# LoRa_Com.net
KiCad netlist of a schematic drawn in Altium Designer
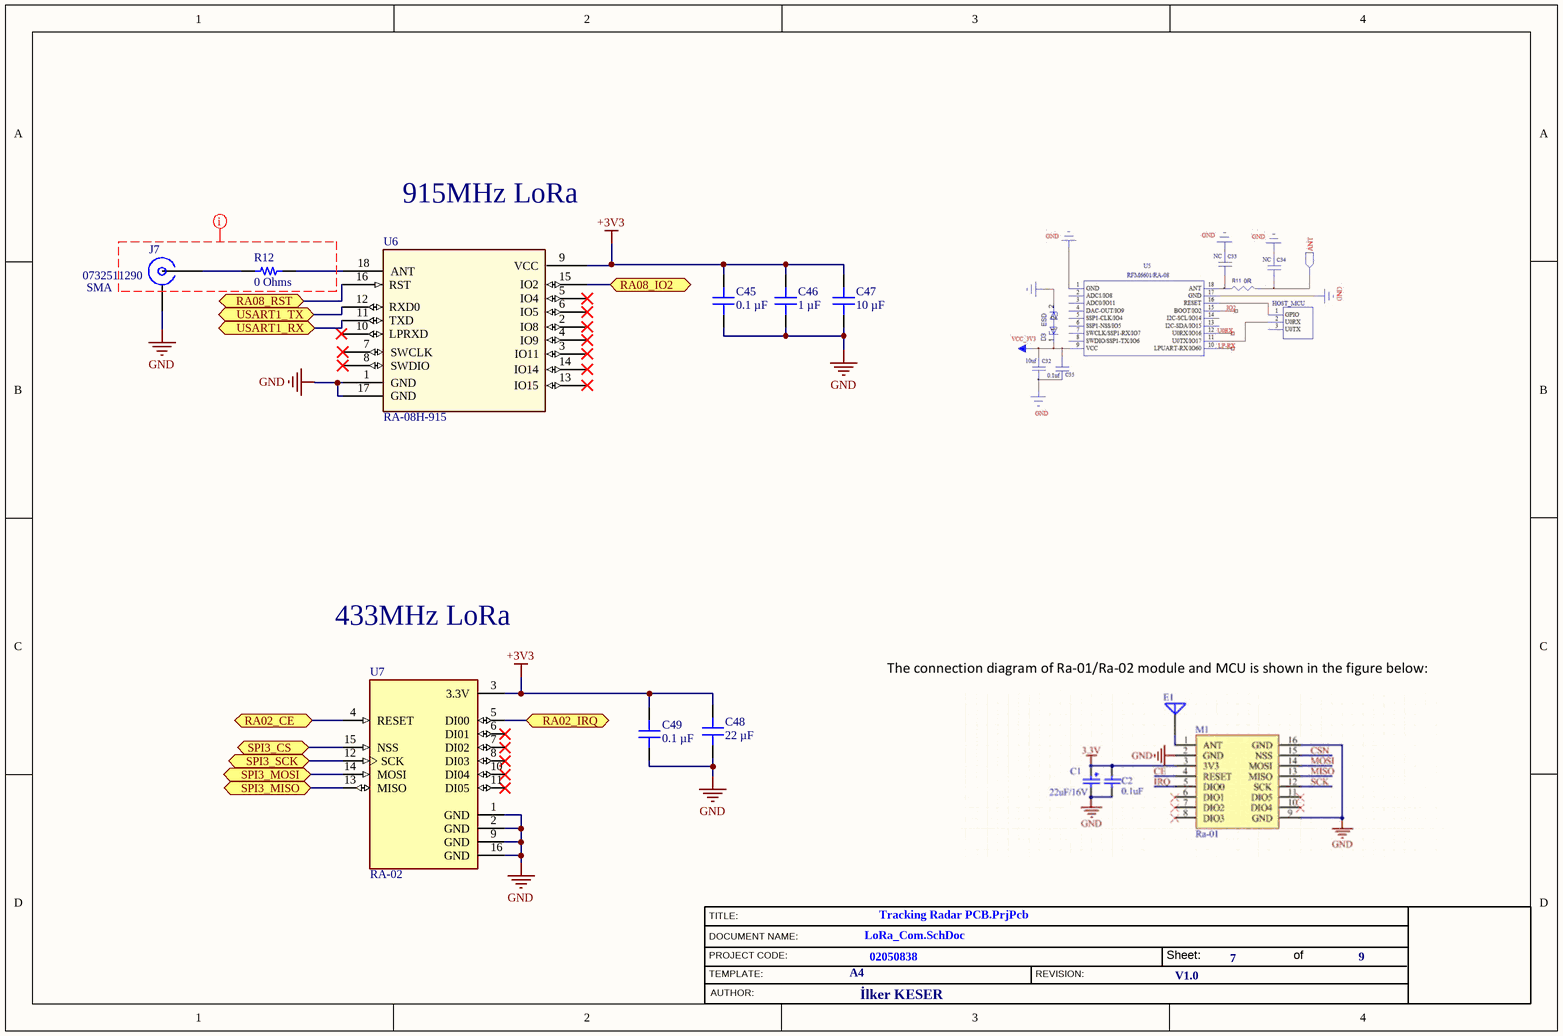
[diagram p0: LoRa_Com.SchDoc]

(export (version "E")
  (design (tool "Eeschema 10.0.6"))
  (components
    (comp (ref "C45")
      (value "0.1 µF")
      (footprint "CAP 0402_1005")
      (description "CAP CER 0.1UF 6.3V X5R 0402")
      (fields
        (field (name "PART NUMBER") "C0402C104M9PAC7867")
        (field (name "CAPACITANCE") "0.1 µF")
        (field (name "MANUFACTURER") "KEMET")
      )
      (libsource (lib "Celestial Altium Library - altium_library") (part "Capacitor"))
    )
    (comp (ref "C46")
      (value "1 µF")
      (footprint "CAP 0402_1005")
      (description "CAP CER 1UF 6.3V X5R 0402")
      (fields
        (field (name "PART NUMBER") "GRM152R60J105ME15D")
        (field (name "CAPACITANCE") "1 µF")
        (field (name "MANUFACTURER") "Murata Electronics")
      )
      (libsource (lib "Celestial Altium Library - altium_library") (part "Capacitor"))
    )
    (comp (ref "C47")
      (value "10 µF")
      (footprint "MURATA GRM188 0603_1608")
      (description "CAP CER 10UF 10V X5R 0603")
      (fields
        (field (name "PART NUMBER") "GRM188R61A106MAALD")
        (field (name "CAPACITANCE") "10 µF")
        (field (name "MANUFACTURER") "Murata Electronics")
      )
      (libsource (lib "Celestial Altium Library - altium_library") (part "Capacitor"))
    )
    (comp (ref "C48")
      (value "22 µF")
      (footprint "MURATA GRM188 0603_1608")
      (description "CAP CER 22UF 16V X5S 0603")
      (fields
        (field (name "PART NUMBER") "GRM188C61C226ME01W")
        (field (name "CAPACITANCE") "22 µF")
        (field (name "MANUFACTURER") "Murata Electronics")
      )
      (libsource (lib "Celestial Altium Library - altium_library") (part "Capacitor"))
    )
    (comp (ref "C49")
      (value "0.1 µF")
      (footprint "CAP 0603_1608")
      (description "CAP CER 0.1UF 16V X7R 0603")
      (fields
        (field (name "PART NUMBER") "885012206046")
        (field (name "CAPACITANCE") "0.1 µF")
        (field (name "MANUFACTURER") "Würth Elektronik")
      )
      (libsource (lib "Celestial Altium Library - altium_library") (part "Capacitor"))
    )
    (comp (ref "J7")
      (value "0732511290")
      (footprint "MOLEX SD-73251-129")
      (description "CONN SMA JACK STR 50OHM EDGE MNT")
      (fields (field (name "CONNECTOR STYLE") "SMA") (field (name "MANUFACTURER") "Molex"))
      (libsource (lib "Celestial Altium Library - altium_library") (part "COAXIAL JACK"))
    )
    (comp (ref "R12")
      (value "0 Ohms")
      (footprint "RES 1206_3216")
      (description "RES SMD 0 OHM JUMPER 1/4W 1206")
      (fields (field (name "PART NUMBER") "CRCW12060000Z0EB") (field (name "MANUFACTURER") "Vishay Dale"))
      (libsource (lib "Celestial Altium Library - altium_library") (part "Resistor"))
    )
    (comp (ref "U6")
      (value "RA-08H-915")
      (footprint "RA-08H-915")
      (description "RF TXRX MODULE 915MHZ LORAWAN")
      (fields (field (name "MANUFACTURER") "Ai-Thinker"))
      (libsource (lib "PCB_Lib") (part "RA-08H-915"))
    )
    (comp (ref "U7")
      (value "RA-02")
      (footprint "RA-02")
      (fields (field (name "MANUFACTURER") "Ai-Thinker"))
      (libsource (lib "PCB_Lib") (part "RA-02"))
    )
  )
  (nets
    (net (code "1") (name "+3V3") (class "Default")
      (node (ref "C45") (pin "2") (pinfunction "2_2") (pintype "passive"))
      (node (ref "C46") (pin "2") (pinfunction "2_2") (pintype "passive"))
      (node (ref "C47") (pin "2") (pinfunction "2_2") (pintype "passive"))
      (node (ref "C48") (pin "2") (pinfunction "2_2") (pintype "passive"))
      (node (ref "C49") (pin "2") (pinfunction "2_2") (pintype "passive"))
      (node (ref "U6") (pin "9") (pinfunction "VCC_9") (pintype "power_in"))
      (node (ref "U7") (pin "3") (pinfunction "3.3V_3") (pintype "power_in"))
    )
    (net (code "2") (name "/RA02_CE") (class "Default")
      (node (ref "U7") (pin "4") (pinfunction "RESET_4") (pintype "input"))
    )
    (net (code "3") (name "/RA02_IRQ") (class "Default")
      (node (ref "U7") (pin "5") (pinfunction "DI00_5") (pintype "bidirectional"))
    )
    (net (code "4") (name "/RA08_IO2") (class "Default")
      (node (ref "U6") (pin "15") (pinfunction "IO2_15") (pintype "bidirectional"))
    )
    (net (code "5") (name "/RA08_RST") (class "Default")
      (node (ref "U6") (pin "16") (pinfunction "RST_16") (pintype "input"))
    )
    (net (code "6") (name "/SPI3_CS") (class "Default")
      (node (ref "U7") (pin "15") (pinfunction "NSS_15") (pintype "input"))
    )
    (net (code "7") (name "/SPI3_MISO") (class "Default")
      (node (ref "U7") (pin "13") (pinfunction "MISO_13") (pintype "bidirectional"))
    )
    (net (code "8") (name "/SPI3_MOSI") (class "Default")
      (node (ref "U7") (pin "14") (pinfunction "MOSI_14") (pintype "input"))
    )
    (net (code "9") (name "/SPI3_SCK") (class "Default")
      (node (ref "U7") (pin "12") (pinfunction "SCK_12") (pintype "input"))
    )
    (net (code "10") (name "/USART1_RX") (class "Default")
      (node (ref "U6") (pin "11") (pinfunction "TXD_11") (pintype "bidirectional"))
    )
    (net (code "11") (name "/USART1_TX") (class "Default")
      (node (ref "U6") (pin "12") (pinfunction "RXD0_12") (pintype "bidirectional"))
    )
    (net (code "12") (name "GND") (class "Default")
      (node (ref "C45") (pin "1") (pinfunction "1_1") (pintype "passive"))
      (node (ref "C46") (pin "1") (pinfunction "1_1") (pintype "passive"))
      (node (ref "C47") (pin "1") (pinfunction "1_1") (pintype "passive"))
      (node (ref "C48") (pin "1") (pinfunction "1_1") (pintype "passive"))
      (node (ref "C49") (pin "1") (pinfunction "1_1") (pintype "passive"))
      (node (ref "J7") (pin "G") (pinfunction "GND_G") (pintype "passive"))
      (node (ref "U6") (pin "1") (pinfunction "GND_1") (pintype "power_in"))
      (node (ref "U6") (pin "17") (pinfunction "GND_17") (pintype "power_in"))
      (node (ref "U7") (pin "1") (pinfunction "GND_1") (pintype "power_in"))
      (node (ref "U7") (pin "16") (pinfunction "GND_16") (pintype "power_in"))
      (node (ref "U7") (pin "2") (pinfunction "GND_2") (pintype "power_in"))
      (node (ref "U7") (pin "9") (pinfunction "GND_9") (pintype "power_in"))
    )
    (net (code "13") (name "Net-(J7-SIGNAL)") (class "Default")
      (node (ref "J7") (pin "S") (pinfunction "SIGNAL_S") (pintype "passive"))
      (node (ref "R12") (pin "1") (pinfunction "1_1") (pintype "passive"))
    )
    (net (code "14") (name "Net-(U6-ANT)") (class "Default")
      (node (ref "R12") (pin "2") (pinfunction "2_2") (pintype "passive"))
      (node (ref "U6") (pin "18") (pinfunction "ANT_18") (pintype "passive"))
    )
    (net (code "15") (name "unconnected-(U6-IO4-Pad5)") (class "Default")
      (node (ref "U6") (pin "5") (pinfunction "IO4_5") (pintype "bidirectional+no_connect"))
    )
    (net (code "16") (name "unconnected-(U6-IO5-Pad6)") (class "Default")
      (node (ref "U6") (pin "6") (pinfunction "IO5_6") (pintype "bidirectional+no_connect"))
    )
    (net (code "17") (name "unconnected-(U6-IO8-Pad2)") (class "Default")
      (node (ref "U6") (pin "2") (pinfunction "IO8_2") (pintype "bidirectional+no_connect"))
    )
    (net (code "18") (name "unconnected-(U6-IO9-Pad4)") (class "Default")
      (node (ref "U6") (pin "4") (pinfunction "IO9_4") (pintype "bidirectional+no_connect"))
    )
    (net (code "19") (name "unconnected-(U6-IO11-Pad3)") (class "Default")
      (node (ref "U6") (pin "3") (pinfunction "IO11_3") (pintype "bidirectional+no_connect"))
    )
    (net (code "20") (name "unconnected-(U6-IO14-Pad14)") (class "Default")
      (node (ref "U6") (pin "14") (pinfunction "IO14_14") (pintype "bidirectional+no_connect"))
    )
    (net (code "21") (name "unconnected-(U6-IO15-Pad13)") (class "Default")
      (node (ref "U6") (pin "13") (pinfunction "IO15_13") (pintype "bidirectional+no_connect"))
    )
    (net (code "22") (name "unconnected-(U6-LPRXD-Pad10)") (class "Default")
      (node (ref "U6") (pin "10") (pinfunction "LPRXD_10") (pintype "bidirectional+no_connect"))
    )
    (net (code "23") (name "unconnected-(U6-SWCLK-Pad7)") (class "Default")
      (node (ref "U6") (pin "7") (pinfunction "SWCLK_7") (pintype "bidirectional+no_connect"))
    )
    (net (code "24") (name "unconnected-(U6-SWDIO-Pad8)") (class "Default")
      (node (ref "U6") (pin "8") (pinfunction "SWDIO_8") (pintype "bidirectional+no_connect"))
    )
    (net (code "25") (name "unconnected-(U7-DI01-Pad6)") (class "Default")
      (node (ref "U7") (pin "6") (pinfunction "DI01_6") (pintype "bidirectional+no_connect"))
    )
    (net (code "26") (name "unconnected-(U7-DI02-Pad7)") (class "Default")
      (node (ref "U7") (pin "7") (pinfunction "DI02_7") (pintype "bidirectional+no_connect"))
    )
    (net (code "27") (name "unconnected-(U7-DI03-Pad8)") (class "Default")
      (node (ref "U7") (pin "8") (pinfunction "DI03_8") (pintype "bidirectional+no_connect"))
    )
    (net (code "28") (name "unconnected-(U7-DI04-Pad10)") (class "Default")
      (node (ref "U7") (pin "10") (pinfunction "DI04_10") (pintype "bidirectional+no_connect"))
    )
    (net (code "29") (name "unconnected-(U7-DI05-Pad11)") (class "Default")
      (node (ref "U7") (pin "11") (pinfunction "DI05_11") (pintype "bidirectional+no_connect"))
    )
  )
)
